# SY8029AIC.net
KiCad netlist of a schematic drawn in Altium Designer
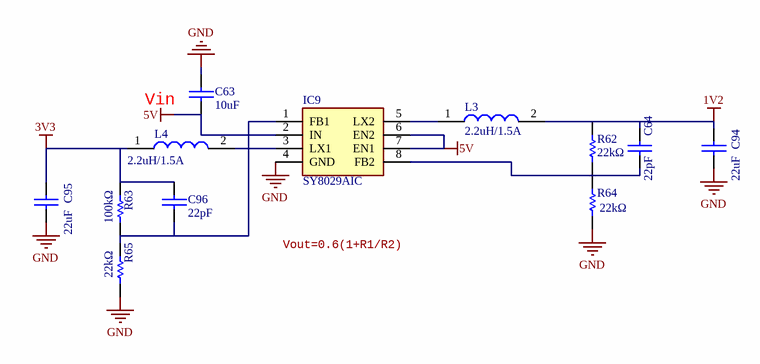
[diagram p0: SY8029AIC.SchDoc]

(export (version "E")
  (design (tool "Eeschema 10.0.6"))
  (components
    (comp (ref "C63")
      (value "10uF")
      (footprint "C_0805")
      (description "贴片电容")
      (libsource (lib "IntLib-Passive") (part "Cap_Chip"))
    )
    (comp (ref "C64")
      (value "22pF")
      (footprint "C_0402")
      (description "贴片电容")
      (libsource (lib "IntLib-Passive") (part "Cap_Chip"))
    )
    (comp (ref "C94")
      (value "22uF")
      (footprint "C_0603")
      (description "贴片电容")
      (libsource (lib "IntLib-Passive") (part "Cap_Chip"))
    )
    (comp (ref "C95")
      (value "22uF")
      (footprint "C_0603")
      (description "贴片电容")
      (libsource (lib "IntLib-Passive") (part "Cap_Chip"))
    )
    (comp (ref "C96")
      (value "22pF")
      (footprint "C_0402")
      (description "贴片电容")
      (libsource (lib "IntLib-Passive") (part "Cap_Chip"))
    )
    (comp (ref "IC9")
      (value "SY8029AIC")
      (footprint "SOT23-8")
      (description "DC-DC降压芯片")
      (libsource (lib "IntLib-IC") (part "SY8029AIC"))
    )
    (comp (ref "L3")
      (value "2.2uH/1.5A")
      (footprint "SamacSys:INDC2520X100N")
      (description "Inductor")
      (fields (field (name "MANUFACTURER_PART_NUMBER") "MLP2520K1R0MT0S1"))
      (libsource (lib "*") (part "MLP2520K1R0MT0S1"))
    )
    (comp (ref "L4")
      (value "2.2uH/1.5A")
      (footprint "SamacSys:INDC2520X100N")
      (description "Inductor")
      (fields (field (name "MANUFACTURER_PART_NUMBER") "MLP2520K1R0MT0S1"))
      (libsource (lib "*") (part "MLP2520K1R0MT0S1"))
    )
    (comp (ref "R62")
      (value "22kΩ")
      (footprint "R_0402")
      (description "贴片电阻")
      (libsource (lib "IntLib-Passive") (part "Res_Chip"))
    )
    (comp (ref "R63")
      (value "100kΩ")
      (footprint "R_0402")
      (description "贴片电阻")
      (libsource (lib "IntLib-Passive") (part "Res_Chip"))
    )
    (comp (ref "R64")
      (value "22kΩ")
      (footprint "R_0402")
      (description "贴片电阻")
      (libsource (lib "IntLib-Passive") (part "Res_Chip"))
    )
    (comp (ref "R65")
      (value "22kΩ")
      (footprint "R_0402")
      (description "贴片电阻")
      (libsource (lib "IntLib-Passive") (part "Res_Chip"))
    )
  )
  (nets
    (net (code "1") (name "1V2") (class "Default")
      (node (ref "C64") (pin "1") (pinfunction "1_1") (pintype "passive"))
      (node (ref "C94") (pin "1") (pinfunction "1_1") (pintype "passive"))
      (node (ref "L3") (pin "2") (pinfunction "2_2") (pintype "passive"))
      (node (ref "R62") (pin "2") (pinfunction "2_2") (pintype "passive"))
    )
    (net (code "2") (name "3V3") (class "Default")
      (node (ref "C95") (pin "1") (pinfunction "1_1") (pintype "passive"))
      (node (ref "C96") (pin "2") (pinfunction "2_2") (pintype "passive"))
      (node (ref "L4") (pin "1") (pinfunction "1_1") (pintype "passive"))
      (node (ref "R63") (pin "1") (pinfunction "1_1") (pintype "passive"))
    )
    (net (code "3") (name "5V") (class "Default")
      (node (ref "C63") (pin "1") (pinfunction "1_1") (pintype "passive"))
      (node (ref "IC9") (pin "2") (pinfunction "IN_2") (pintype "passive"))
      (node (ref "IC9") (pin "6") (pinfunction "EN2_6") (pintype "passive"))
      (node (ref "IC9") (pin "7") (pinfunction "EN1_7") (pintype "passive"))
    )
    (net (code "4") (name "GND") (class "Default")
      (node (ref "C63") (pin "2") (pinfunction "2_2") (pintype "passive"))
      (node (ref "C94") (pin "2") (pinfunction "2_2") (pintype "passive"))
      (node (ref "C95") (pin "2") (pinfunction "2_2") (pintype "passive"))
      (node (ref "IC9") (pin "4") (pinfunction "GND_4") (pintype "passive"))
      (node (ref "R64") (pin "1") (pinfunction "1_1") (pintype "passive"))
      (node (ref "R65") (pin "2") (pinfunction "2_2") (pintype "passive"))
    )
    (net (code "5") (name "Net-(IC9-FB1)") (class "Default")
      (node (ref "C96") (pin "1") (pinfunction "1_1") (pintype "passive"))
      (node (ref "IC9") (pin "1") (pinfunction "FB1_1") (pintype "passive"))
      (node (ref "R63") (pin "2") (pinfunction "2_2") (pintype "passive"))
      (node (ref "R65") (pin "1") (pinfunction "1_1") (pintype "passive"))
    )
    (net (code "6") (name "Net-(IC9-FB2)") (class "Default")
      (node (ref "C64") (pin "2") (pinfunction "2_2") (pintype "passive"))
      (node (ref "IC9") (pin "8") (pinfunction "FB2_8") (pintype "passive"))
      (node (ref "R62") (pin "1") (pinfunction "1_1") (pintype "passive"))
      (node (ref "R64") (pin "2") (pinfunction "2_2") (pintype "passive"))
    )
    (net (code "7") (name "Net-(IC9-LX1)") (class "Default")
      (node (ref "IC9") (pin "3") (pinfunction "LX1_3") (pintype "passive"))
      (node (ref "L4") (pin "2") (pinfunction "2_2") (pintype "passive"))
    )
    (net (code "8") (name "Net-(IC9-LX2)") (class "Default")
      (node (ref "IC9") (pin "5") (pinfunction "LX2_5") (pintype "passive"))
      (node (ref "L3") (pin "1") (pinfunction "1_1") (pintype "passive"))
    )
  )
)
